# BRAINCHIP.net
KiCad netlist of a schematic drawn in EAGLE
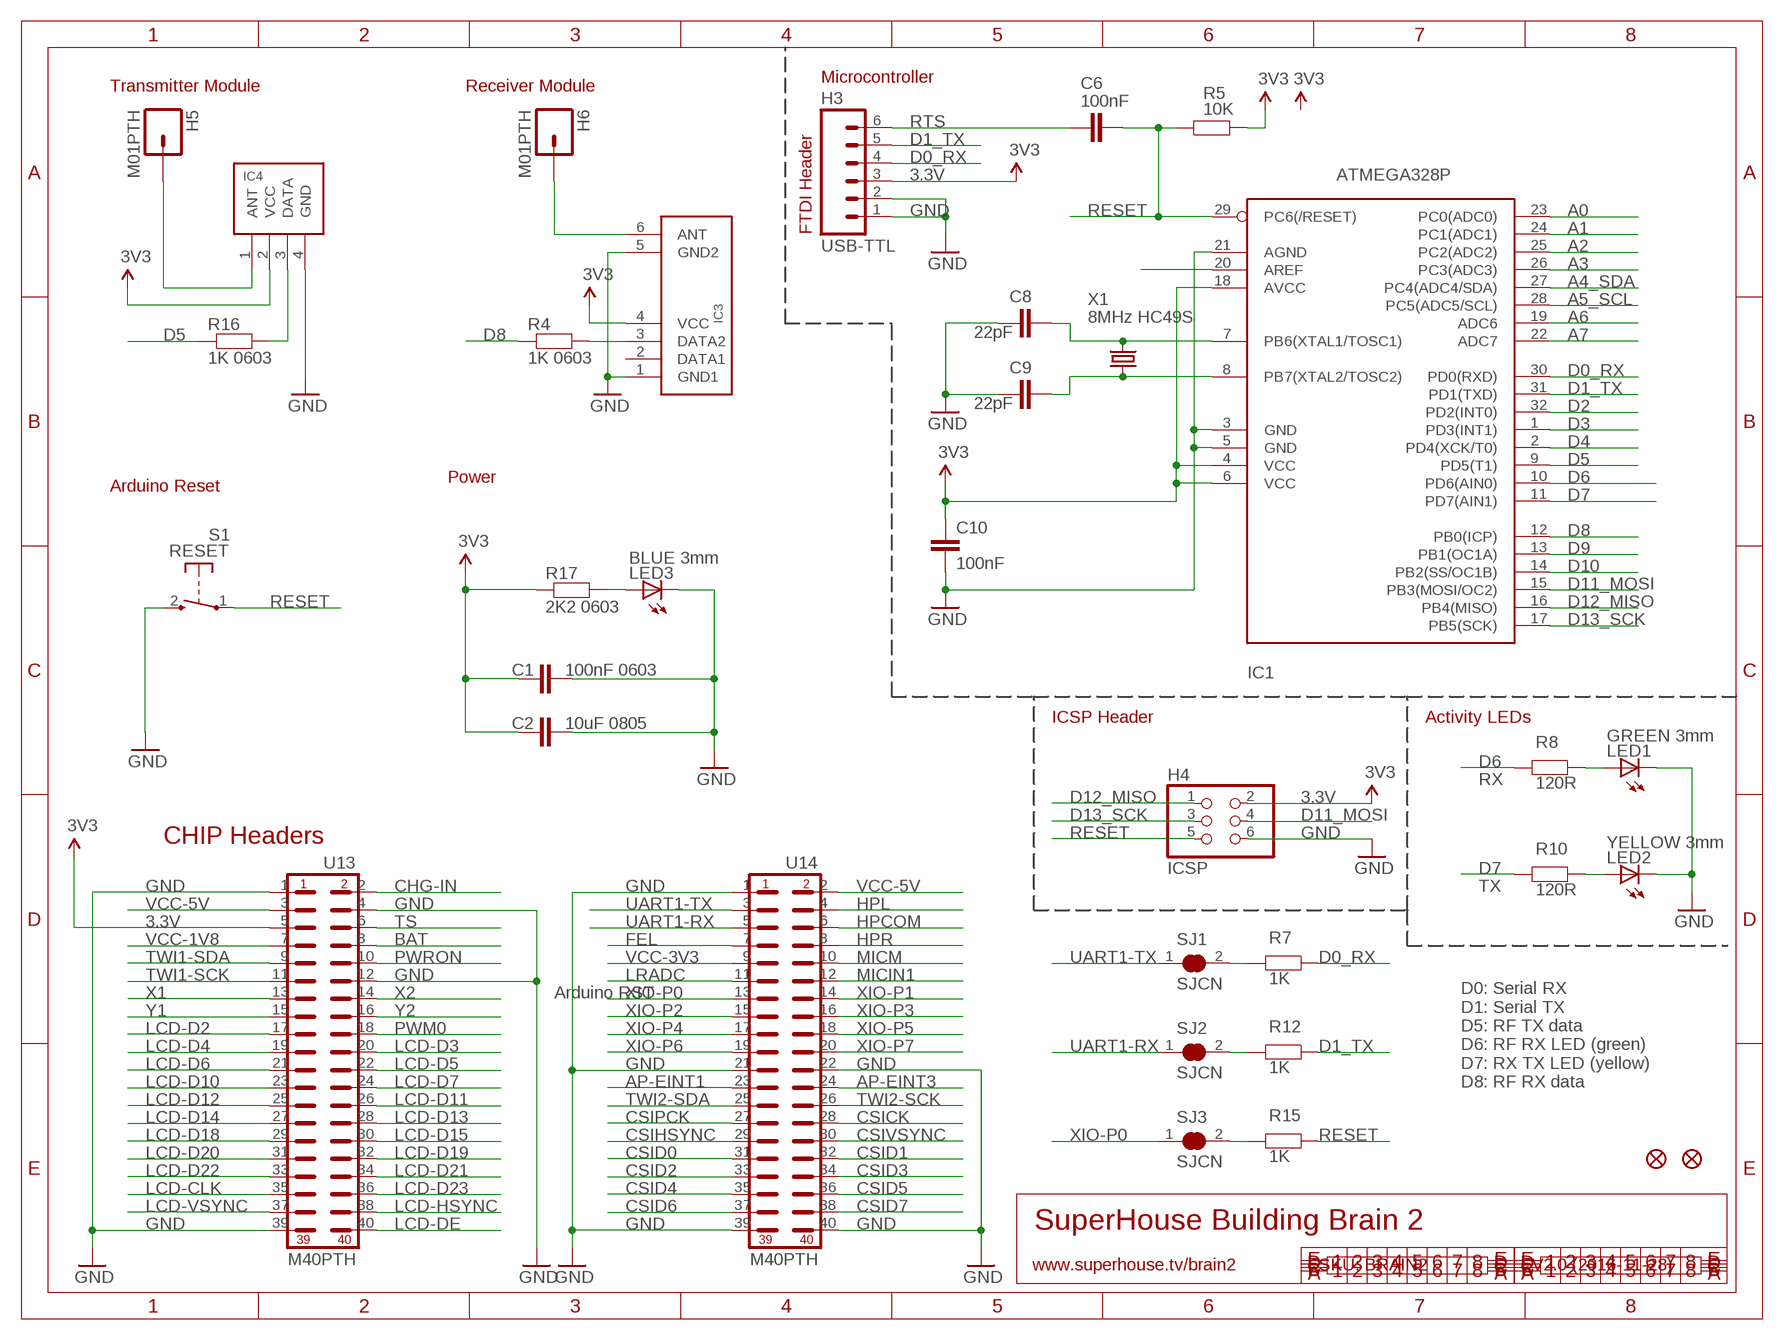
[diagram p0: schematic, sheet 1]

(export (version "E")
  (design (tool "Eeschema 10.0.6"))
  (components
    (comp (ref "C1")
      (value "100nF 0603")
      (footprint "eagle-import:0603")
      (libsource (lib "eagle-import") (part "CAP0603"))
    )
    (comp (ref "C2")
      (value "10uF 0805")
      (footprint "eagle-import:C0805")
      (libsource (lib "eagle-import") (part "C-EUC0805"))
    )
    (comp (ref "C6")
      (value "100nF")
      (footprint "eagle-import:0603")
      (libsource (lib "eagle-import") (part "freetronics-master-v1.1_CAP0603"))
    )
    (comp (ref "C8")
      (value "22pF")
      (footprint "eagle-import:0603")
      (libsource (lib "eagle-import") (part "freetronics-master-v1.1_CAP0603"))
    )
    (comp (ref "C9")
      (value "22pF")
      (footprint "eagle-import:0603")
      (libsource (lib "eagle-import") (part "freetronics-master-v1.1_CAP0603"))
    )
    (comp (ref "C10")
      (value "100nF")
      (footprint "eagle-import:0603")
      (libsource (lib "eagle-import") (part "freetronics-master-v1.1_CAP0603"))
    )
    (comp (ref "H3")
      (value "USB-TTL")
      (footprint "eagle-import:1X06")
      (libsource (lib "eagle-import") (part "M06SIP"))
    )
    (comp (ref "H4")
      (value "ICSP")
      (footprint "eagle-import:2X03")
      (libsource (lib "eagle-import") (part "PINHD-2X3"))
    )
    (comp (ref "H5")
      (value "M01PTH")
      (footprint "eagle-import:1X01")
      (libsource (lib "eagle-import") (part "M01PTH"))
    )
    (comp (ref "H6")
      (value "M01PTH")
      (footprint "eagle-import:1X01")
      (libsource (lib "eagle-import") (part "M01PTH"))
    )
    (comp (ref "IC1")
      (value "ATMEGA328P")
      (footprint "eagle-import:TQFP32-08")
      (libsource (lib "eagle-import") (part "AVR-MEGA8-AI"))
    )
    (comp (ref "IC3")
      (value "RXB1")
      (footprint "eagle-import:RX-B1-SHORT-FLAT")
      (libsource (lib "eagle-import") (part "RXB1SHORTFLAT"))
    )
    (comp (ref "IC4")
      (value "TX-C1FLAT")
      (footprint "eagle-import:TX-C1-FLAT")
      (libsource (lib "eagle-import") (part "TX-C1FLAT"))
    )
    (comp (ref "LED1")
      (value "GREEN 3mm")
      (footprint "eagle-import:LED3MM")
      (libsource (lib "eagle-import") (part "LED3MM"))
    )
    (comp (ref "LED2")
      (value "YELLOW 3mm")
      (footprint "eagle-import:LED3MM")
      (libsource (lib "eagle-import") (part "LED3MM"))
    )
    (comp (ref "LED3")
      (value "BLUE 3mm")
      (footprint "eagle-import:LED3MM")
      (libsource (lib "eagle-import") (part "LED3MM"))
    )
    (comp (ref "R4")
      (value "1K 0603")
      (footprint "eagle-import:0603")
      (libsource (lib "eagle-import") (part "RESISTOR0603"))
    )
    (comp (ref "R5")
      (value "10K")
      (footprint "eagle-import:0603")
      (libsource (lib "eagle-import") (part "freetronics-master-v1.1_RESISTOR0603"))
    )
    (comp (ref "R7")
      (value "1K")
      (footprint "eagle-import:0603")
      (libsource (lib "eagle-import") (part "freetronics-master-v1.1_RESISTOR0603"))
    )
    (comp (ref "R8")
      (value "120R")
      (footprint "eagle-import:0603")
      (libsource (lib "eagle-import") (part "freetronics-master-v1.1_RESISTOR0603"))
    )
    (comp (ref "R10")
      (value "120R")
      (footprint "eagle-import:0603")
      (libsource (lib "eagle-import") (part "freetronics-master-v1.1_RESISTOR0603"))
    )
    (comp (ref "R12")
      (value "1K")
      (footprint "eagle-import:0603")
      (libsource (lib "eagle-import") (part "freetronics-master-v1.1_RESISTOR0603"))
    )
    (comp (ref "R15")
      (value "1K")
      (footprint "eagle-import:0603")
      (libsource (lib "eagle-import") (part "freetronics-master-v1.1_RESISTOR0603"))
    )
    (comp (ref "R16")
      (value "1K 0603")
      (footprint "eagle-import:0603")
      (libsource (lib "eagle-import") (part "RESISTOR0603"))
    )
    (comp (ref "R17")
      (value "2K2 0603")
      (footprint "eagle-import:0603")
      (libsource (lib "eagle-import") (part "RESISTOR0603"))
    )
    (comp (ref "S1")
      (value "RESET")
      (footprint "eagle-import:TACTILE_SWITCH_SMD_2PIN_TINY")
      (libsource (lib "eagle-import") (part "TAC_SWITCH_2PIN"))
    )
    (comp (ref "SJ1")
      (value "SJCN")
      (footprint "eagle-import:SJC")
      (libsource (lib "eagle-import") (part "SJCN"))
    )
    (comp (ref "SJ2")
      (value "SJCN")
      (footprint "eagle-import:SJC")
      (libsource (lib "eagle-import") (part "SJCN"))
    )
    (comp (ref "SJ3")
      (value "SJCN")
      (footprint "eagle-import:SJC")
      (libsource (lib "eagle-import") (part "SJCN"))
    )
    (comp (ref "U$5")
      (value "FIDUCIAL1X2.5")
      (footprint "eagle-import:FIDUCIAL-1X2.5")
      (libsource (lib "eagle-import") (part "FIDUCIAL1X2.5"))
    )
    (comp (ref "U$6")
      (value "FIDUCIAL1X2.5")
      (footprint "eagle-import:FIDUCIAL-1X2.5")
      (libsource (lib "eagle-import") (part "FIDUCIAL1X2.5"))
    )
    (comp (ref "U13")
      (value "M40PTH")
      (footprint "eagle-import:2X20")
      (libsource (lib "eagle-import") (part "M40PTH"))
    )
    (comp (ref "U14")
      (value "M40PTH")
      (footprint "eagle-import:2X20")
      (libsource (lib "eagle-import") (part "M40PTH"))
    )
    (comp (ref "X1")
      (value "8MHz HC49S")
      (footprint "eagle-import:HC49U-V")
      (libsource (lib "eagle-import") (part "CRYSTALHC49UV"))
    )
  )
  (nets
    (net (code "1") (name "/A0") (class "Default")
      (node (ref "IC1") (pin "23") (pinfunction "PC0(ADC0)_23") (pintype "bidirectional"))
    )
    (net (code "2") (name "/A1") (class "Default")
      (node (ref "IC1") (pin "24") (pinfunction "PC1(ADC1)_24") (pintype "bidirectional"))
    )
    (net (code "3") (name "/A2") (class "Default")
      (node (ref "IC1") (pin "25") (pinfunction "PC2(ADC2)_25") (pintype "bidirectional"))
    )
    (net (code "4") (name "/A3") (class "Default")
      (node (ref "IC1") (pin "26") (pinfunction "PC3(ADC3)_26") (pintype "bidirectional"))
    )
    (net (code "5") (name "/A4_SDA") (class "Default")
      (node (ref "IC1") (pin "27") (pinfunction "PC4(ADC4/SDA)_27") (pintype "bidirectional"))
    )
    (net (code "6") (name "/A5_SCL") (class "Default")
      (node (ref "IC1") (pin "28") (pinfunction "PC5(ADC5/SCL)_28") (pintype "bidirectional"))
    )
    (net (code "7") (name "/A6") (class "Default")
      (node (ref "IC1") (pin "19") (pinfunction "ADC6_19") (pintype "bidirectional"))
    )
    (net (code "8") (name "/A7") (class "Default")
      (node (ref "IC1") (pin "22") (pinfunction "ADC7_22") (pintype "bidirectional"))
    )
    (net (code "9") (name "/AP-EINT1") (class "Default")
      (node (ref "U14") (pin "23") (pinfunction "23_23") (pintype "passive"))
    )
    (net (code "10") (name "/AP-EINT3") (class "Default")
      (node (ref "U14") (pin "24") (pinfunction "24_24") (pintype "passive"))
    )
    (net (code "11") (name "/BAT") (class "Default")
      (node (ref "U13") (pin "8") (pinfunction "8_8") (pintype "passive"))
    )
    (net (code "12") (name "/CHG-IN") (class "Default")
      (node (ref "U13") (pin "2") (pinfunction "2_2") (pintype "passive"))
    )
    (net (code "13") (name "/CSICK") (class "Default")
      (node (ref "U14") (pin "28") (pinfunction "28_28") (pintype "passive"))
    )
    (net (code "14") (name "/CSID0") (class "Default")
      (node (ref "U14") (pin "31") (pinfunction "31_31") (pintype "passive"))
    )
    (net (code "15") (name "/CSID1") (class "Default")
      (node (ref "U14") (pin "32") (pinfunction "32_32") (pintype "passive"))
    )
    (net (code "16") (name "/CSID2") (class "Default")
      (node (ref "U14") (pin "33") (pinfunction "33_33") (pintype "passive"))
    )
    (net (code "17") (name "/CSID3") (class "Default")
      (node (ref "U14") (pin "34") (pinfunction "34_34") (pintype "passive"))
    )
    (net (code "18") (name "/CSID4") (class "Default")
      (node (ref "U14") (pin "35") (pinfunction "35_35") (pintype "passive"))
    )
    (net (code "19") (name "/CSID5") (class "Default")
      (node (ref "U14") (pin "36") (pinfunction "36_36") (pintype "passive"))
    )
    (net (code "20") (name "/CSID6") (class "Default")
      (node (ref "U14") (pin "37") (pinfunction "37_37") (pintype "passive"))
    )
    (net (code "21") (name "/CSID7") (class "Default")
      (node (ref "U14") (pin "38") (pinfunction "38_38") (pintype "passive"))
    )
    (net (code "22") (name "/CSIHSYNC") (class "Default")
      (node (ref "U14") (pin "29") (pinfunction "29_29") (pintype "passive"))
    )
    (net (code "23") (name "/CSIPCK") (class "Default")
      (node (ref "U14") (pin "27") (pinfunction "27_27") (pintype "passive"))
    )
    (net (code "24") (name "/CSIVSYNC") (class "Default")
      (node (ref "U14") (pin "30") (pinfunction "30_30") (pintype "passive"))
    )
    (net (code "25") (name "/D0_RX") (class "Default")
      (node (ref "H3") (pin "4") (pinfunction "4_4") (pintype "passive"))
      (node (ref "IC1") (pin "30") (pinfunction "PD0(RXD)_30") (pintype "bidirectional"))
      (node (ref "R7") (pin "1") (pinfunction "1_1") (pintype "passive"))
    )
    (net (code "26") (name "/D1_TX") (class "Default")
      (node (ref "H3") (pin "5") (pinfunction "5_5") (pintype "passive"))
      (node (ref "IC1") (pin "31") (pinfunction "PD1(TXD)_31") (pintype "bidirectional"))
      (node (ref "R12") (pin "1") (pinfunction "1_1") (pintype "passive"))
    )
    (net (code "27") (name "/D2") (class "Default")
      (node (ref "IC1") (pin "32") (pinfunction "PD2(INT0)_32") (pintype "bidirectional"))
    )
    (net (code "28") (name "/D3") (class "Default")
      (node (ref "IC1") (pin "1") (pinfunction "PD3(INT1)_1") (pintype "bidirectional"))
    )
    (net (code "29") (name "/D4") (class "Default")
      (node (ref "IC1") (pin "2") (pinfunction "PD4(XCK/T0)_2") (pintype "bidirectional"))
    )
    (net (code "30") (name "/D5") (class "Default")
      (node (ref "IC1") (pin "9") (pinfunction "PD5(T1)_9") (pintype "bidirectional"))
      (node (ref "R16") (pin "1") (pinfunction "1_1") (pintype "passive"))
    )
    (net (code "31") (name "/D6") (class "Default")
      (node (ref "IC1") (pin "10") (pinfunction "PD6(AIN0)_10") (pintype "bidirectional"))
      (node (ref "R8") (pin "2") (pinfunction "2_2") (pintype "passive"))
    )
    (net (code "32") (name "/D7") (class "Default")
      (node (ref "IC1") (pin "11") (pinfunction "PD7(AIN1)_11") (pintype "bidirectional"))
      (node (ref "R10") (pin "2") (pinfunction "2_2") (pintype "passive"))
    )
    (net (code "33") (name "/D8") (class "Default")
      (node (ref "IC1") (pin "12") (pinfunction "PB0(ICP)_12") (pintype "bidirectional"))
      (node (ref "R4") (pin "1") (pinfunction "1_1") (pintype "passive"))
    )
    (net (code "34") (name "/D9") (class "Default")
      (node (ref "IC1") (pin "13") (pinfunction "PB1(OC1A)_13") (pintype "bidirectional"))
    )
    (net (code "35") (name "/D10") (class "Default")
      (node (ref "IC1") (pin "14") (pinfunction "PB2(SS/OC1B)_14") (pintype "bidirectional"))
    )
    (net (code "36") (name "/D11_MOSI") (class "Default")
      (node (ref "H4") (pin "4") (pinfunction "4_4") (pintype "passive"))
      (node (ref "IC1") (pin "15") (pinfunction "PB3(MOSI/OC2)_15") (pintype "bidirectional"))
    )
    (net (code "37") (name "/D12_MISO") (class "Default")
      (node (ref "H4") (pin "1") (pinfunction "1_1") (pintype "passive"))
      (node (ref "IC1") (pin "16") (pinfunction "PB4(MISO)_16") (pintype "bidirectional"))
    )
    (net (code "38") (name "/D13_SCK") (class "Default")
      (node (ref "H4") (pin "3") (pinfunction "3_3") (pintype "passive"))
      (node (ref "IC1") (pin "17") (pinfunction "PB5(SCK)_17") (pintype "bidirectional"))
    )
    (net (code "39") (name "/FEL") (class "Default")
      (node (ref "U14") (pin "7") (pinfunction "7_7") (pintype "passive"))
    )
    (net (code "40") (name "/HPCOM") (class "Default")
      (node (ref "U14") (pin "6") (pinfunction "6_6") (pintype "passive"))
    )
    (net (code "41") (name "/HPL") (class "Default")
      (node (ref "U14") (pin "4") (pinfunction "4_4") (pintype "passive"))
    )
    (net (code "42") (name "/HPR") (class "Default")
      (node (ref "U14") (pin "8") (pinfunction "8_8") (pintype "passive"))
    )
    (net (code "43") (name "/LCD-CLK") (class "Default")
      (node (ref "U13") (pin "35") (pinfunction "35_35") (pintype "passive"))
    )
    (net (code "44") (name "/LCD-D2") (class "Default")
      (node (ref "U13") (pin "17") (pinfunction "17_17") (pintype "passive"))
    )
    (net (code "45") (name "/LCD-D3") (class "Default")
      (node (ref "U13") (pin "20") (pinfunction "20_20") (pintype "passive"))
    )
    (net (code "46") (name "/LCD-D4") (class "Default")
      (node (ref "U13") (pin "19") (pinfunction "19_19") (pintype "passive"))
    )
    (net (code "47") (name "/LCD-D5") (class "Default")
      (node (ref "U13") (pin "22") (pinfunction "22_22") (pintype "passive"))
    )
    (net (code "48") (name "/LCD-D6") (class "Default")
      (node (ref "U13") (pin "21") (pinfunction "21_21") (pintype "passive"))
    )
    (net (code "49") (name "/LCD-D7") (class "Default")
      (node (ref "U13") (pin "24") (pinfunction "24_24") (pintype "passive"))
    )
    (net (code "50") (name "/LCD-D10") (class "Default")
      (node (ref "U13") (pin "23") (pinfunction "23_23") (pintype "passive"))
    )
    (net (code "51") (name "/LCD-D11") (class "Default")
      (node (ref "U13") (pin "26") (pinfunction "26_26") (pintype "passive"))
    )
    (net (code "52") (name "/LCD-D12") (class "Default")
      (node (ref "U13") (pin "25") (pinfunction "25_25") (pintype "passive"))
    )
    (net (code "53") (name "/LCD-D13") (class "Default")
      (node (ref "U13") (pin "28") (pinfunction "28_28") (pintype "passive"))
    )
    (net (code "54") (name "/LCD-D14") (class "Default")
      (node (ref "U13") (pin "27") (pinfunction "27_27") (pintype "passive"))
    )
    (net (code "55") (name "/LCD-D15") (class "Default")
      (node (ref "U13") (pin "30") (pinfunction "30_30") (pintype "passive"))
    )
    (net (code "56") (name "/LCD-D18") (class "Default")
      (node (ref "U13") (pin "29") (pinfunction "29_29") (pintype "passive"))
    )
    (net (code "57") (name "/LCD-D19") (class "Default")
      (node (ref "U13") (pin "32") (pinfunction "32_32") (pintype "passive"))
    )
    (net (code "58") (name "/LCD-D20") (class "Default")
      (node (ref "U13") (pin "31") (pinfunction "31_31") (pintype "passive"))
    )
    (net (code "59") (name "/LCD-D21") (class "Default")
      (node (ref "U13") (pin "34") (pinfunction "34_34") (pintype "passive"))
    )
    (net (code "60") (name "/LCD-D22") (class "Default")
      (node (ref "U13") (pin "33") (pinfunction "33_33") (pintype "passive"))
    )
    (net (code "61") (name "/LCD-D23") (class "Default")
      (node (ref "U13") (pin "36") (pinfunction "36_36") (pintype "passive"))
    )
    (net (code "62") (name "/LCD-DE") (class "Default")
      (node (ref "U13") (pin "40") (pinfunction "40_40") (pintype "passive"))
    )
    (net (code "63") (name "/LCD-HSYNC") (class "Default")
      (node (ref "U13") (pin "38") (pinfunction "38_38") (pintype "passive"))
    )
    (net (code "64") (name "/LCD-VSYNC") (class "Default")
      (node (ref "U13") (pin "37") (pinfunction "37_37") (pintype "passive"))
    )
    (net (code "65") (name "/LRADC") (class "Default")
      (node (ref "U14") (pin "11") (pinfunction "11_11") (pintype "passive"))
    )
    (net (code "66") (name "/MICIN1") (class "Default")
      (node (ref "U14") (pin "12") (pinfunction "12_12") (pintype "passive"))
    )
    (net (code "67") (name "/MICM") (class "Default")
      (node (ref "U14") (pin "10") (pinfunction "10_10") (pintype "passive"))
    )
    (net (code "68") (name "/PWM0") (class "Default")
      (node (ref "U13") (pin "18") (pinfunction "18_18") (pintype "passive"))
    )
    (net (code "69") (name "/PWRON") (class "Default")
      (node (ref "U13") (pin "10") (pinfunction "10_10") (pintype "passive"))
    )
    (net (code "70") (name "/RESET") (class "Default")
      (node (ref "C6") (pin "2") (pinfunction "2_2") (pintype "passive"))
      (node (ref "H4") (pin "5") (pinfunction "5_5") (pintype "passive"))
      (node (ref "IC1") (pin "29") (pinfunction "PC6(/RESET)_29") (pintype "bidirectional"))
      (node (ref "R15") (pin "1") (pinfunction "1_1") (pintype "passive"))
      (node (ref "R5") (pin "1") (pinfunction "1_1") (pintype "passive"))
      (node (ref "S1") (pin "1") (pinfunction "P_1") (pintype "passive"))
    )
    (net (code "71") (name "/RTS") (class "Default")
      (node (ref "C6") (pin "1") (pinfunction "1_1") (pintype "passive"))
      (node (ref "H3") (pin "6") (pinfunction "6_6") (pintype "passive"))
    )
    (net (code "72") (name "/TS") (class "Default")
      (node (ref "U13") (pin "6") (pinfunction "6_6") (pintype "passive"))
    )
    (net (code "73") (name "/TWI1-SCK") (class "Default")
      (node (ref "U13") (pin "11") (pinfunction "11_11") (pintype "passive"))
    )
    (net (code "74") (name "/TWI1-SDA") (class "Default")
      (node (ref "U13") (pin "9") (pinfunction "9_9") (pintype "passive"))
    )
    (net (code "75") (name "/TWI2-SCK") (class "Default")
      (node (ref "U14") (pin "26") (pinfunction "26_26") (pintype "passive"))
    )
    (net (code "76") (name "/TWI2-SDA") (class "Default")
      (node (ref "U14") (pin "25") (pinfunction "25_25") (pintype "passive"))
    )
    (net (code "77") (name "/UART1-RX") (class "Default")
      (node (ref "SJ2") (pin "1") (pinfunction "1_1") (pintype "passive"))
      (node (ref "U14") (pin "5") (pinfunction "5_5") (pintype "passive"))
    )
    (net (code "78") (name "/UART1-TX") (class "Default")
      (node (ref "SJ1") (pin "1") (pinfunction "1_1") (pintype "passive"))
      (node (ref "U14") (pin "3") (pinfunction "3_3") (pintype "passive"))
    )
    (net (code "79") (name "/VCC-1V8") (class "Default")
      (node (ref "U13") (pin "7") (pinfunction "7_7") (pintype "passive"))
    )
    (net (code "80") (name "/VCC-3V3") (class "Default")
      (node (ref "U14") (pin "9") (pinfunction "9_9") (pintype "passive"))
    )
    (net (code "81") (name "/VCC-5V") (class "Default")
      (node (ref "U13") (pin "3") (pinfunction "3_3") (pintype "passive"))
      (node (ref "U14") (pin "2") (pinfunction "2_2") (pintype "passive"))
    )
    (net (code "82") (name "/X1") (class "Default")
      (node (ref "U13") (pin "13") (pinfunction "13_13") (pintype "passive"))
    )
    (net (code "83") (name "/X2") (class "Default")
      (node (ref "U13") (pin "14") (pinfunction "14_14") (pintype "passive"))
    )
    (net (code "84") (name "/XIO-P0") (class "Default")
      (node (ref "SJ3") (pin "1") (pinfunction "1_1") (pintype "passive"))
      (node (ref "U14") (pin "13") (pinfunction "13_13") (pintype "passive"))
    )
    (net (code "85") (name "/XIO-P1") (class "Default")
      (node (ref "U14") (pin "14") (pinfunction "14_14") (pintype "passive"))
    )
    (net (code "86") (name "/XIO-P2") (class "Default")
      (node (ref "U14") (pin "15") (pinfunction "15_15") (pintype "passive"))
    )
    (net (code "87") (name "/XIO-P3") (class "Default")
      (node (ref "U14") (pin "16") (pinfunction "16_16") (pintype "passive"))
    )
    (net (code "88") (name "/XIO-P4") (class "Default")
      (node (ref "U14") (pin "17") (pinfunction "17_17") (pintype "passive"))
    )
    (net (code "89") (name "/XIO-P5") (class "Default")
      (node (ref "U14") (pin "18") (pinfunction "18_18") (pintype "passive"))
    )
    (net (code "90") (name "/XIO-P6") (class "Default")
      (node (ref "U14") (pin "19") (pinfunction "19_19") (pintype "passive"))
    )
    (net (code "91") (name "/XIO-P7") (class "Default")
      (node (ref "U14") (pin "20") (pinfunction "20_20") (pintype "passive"))
    )
    (net (code "92") (name "/Y1") (class "Default")
      (node (ref "U13") (pin "15") (pinfunction "15_15") (pintype "passive"))
    )
    (net (code "93") (name "/Y2") (class "Default")
      (node (ref "U13") (pin "16") (pinfunction "16_16") (pintype "passive"))
    )
    (net (code "94") (name "3V3") (class "Default")
      (node (ref "C1") (pin "1") (pinfunction "1_1") (pintype "passive"))
      (node (ref "C10") (pin "1") (pinfunction "1_1") (pintype "passive"))
      (node (ref "C2") (pin "2") (pinfunction "2_2") (pintype "passive"))
      (node (ref "H3") (pin "3") (pinfunction "3_3") (pintype "passive"))
      (node (ref "H4") (pin "2") (pinfunction "2_2") (pintype "passive"))
      (node (ref "IC1") (pin "18") (pinfunction "AVCC_18") (pintype "bidirectional"))
      (node (ref "IC1") (pin "4") (pinfunction "VCC_4") (pintype "bidirectional"))
      (node (ref "IC1") (pin "6") (pinfunction "VCC_6") (pintype "bidirectional"))
      (node (ref "IC3") (pin "4") (pinfunction "VCC_4") (pintype "bidirectional"))
      (node (ref "IC4") (pin "2") (pinfunction "VCC_2") (pintype "power_in"))
      (node (ref "R17") (pin "1") (pinfunction "1_1") (pintype "passive"))
      (node (ref "R5") (pin "2") (pinfunction "2_2") (pintype "passive"))
      (node (ref "U13") (pin "5") (pinfunction "5_5") (pintype "passive"))
    )
    (net (code "95") (name "GND") (class "Default")
      (node (ref "C1") (pin "2") (pinfunction "2_2") (pintype "passive"))
      (node (ref "C10") (pin "2") (pinfunction "2_2") (pintype "passive"))
      (node (ref "C2") (pin "1") (pinfunction "1_1") (pintype "passive"))
      (node (ref "C8") (pin "1") (pinfunction "1_1") (pintype "passive"))
      (node (ref "C9") (pin "1") (pinfunction "1_1") (pintype "passive"))
      (node (ref "H3") (pin "1") (pinfunction "1_1") (pintype "passive"))
      (node (ref "H3") (pin "2") (pinfunction "2_2") (pintype "passive"))
      (node (ref "H4") (pin "6") (pinfunction "6_6") (pintype "passive"))
      (node (ref "IC1") (pin "21") (pinfunction "AGND_21") (pintype "bidirectional"))
      (node (ref "IC1") (pin "3") (pinfunction "GND_3") (pintype "bidirectional"))
      (node (ref "IC1") (pin "5") (pinfunction "GND_5") (pintype "bidirectional"))
      (node (ref "IC3") (pin "1") (pinfunction "GND1_1") (pintype "bidirectional"))
      (node (ref "IC3") (pin "5") (pinfunction "GND2_5") (pintype "bidirectional"))
      (node (ref "IC4") (pin "4") (pinfunction "GND_4") (pintype "power_in"))
      (node (ref "LED1") (pin "K") (pinfunction "C_K") (pintype "passive"))
      (node (ref "LED2") (pin "K") (pinfunction "C_K") (pintype "passive"))
      (node (ref "LED3") (pin "K") (pinfunction "C_K") (pintype "passive"))
      (node (ref "S1") (pin "2") (pinfunction "S_2") (pintype "passive"))
      (node (ref "U13") (pin "1") (pinfunction "1_1") (pintype "passive"))
      (node (ref "U13") (pin "12") (pinfunction "12_12") (pintype "passive"))
      (node (ref "U13") (pin "39") (pinfunction "39_39") (pintype "passive"))
      (node (ref "U13") (pin "4") (pinfunction "4_4") (pintype "passive"))
      (node (ref "U14") (pin "1") (pinfunction "1_1") (pintype "passive"))
      (node (ref "U14") (pin "21") (pinfunction "21_21") (pintype "passive"))
      (node (ref "U14") (pin "22") (pinfunction "22_22") (pintype "passive"))
      (node (ref "U14") (pin "39") (pinfunction "39_39") (pintype "passive"))
      (node (ref "U14") (pin "40") (pinfunction "40_40") (pintype "passive"))
    )
    (net (code "96") (name "Net-(IC1-PB6(XTAL1{slash}TOSC1))") (class "Default")
      (node (ref "C8") (pin "2") (pinfunction "2_2") (pintype "passive"))
      (node (ref "IC1") (pin "7") (pinfunction "PB6(XTAL1/TOSC1)_7") (pintype "bidirectional"))
      (node (ref "X1") (pin "2") (pinfunction "2_2") (pintype "passive"))
    )
    (net (code "97") (name "Net-(IC1-PB7(XTAL2{slash}TOSC2))") (class "Default")
      (node (ref "C9") (pin "2") (pinfunction "2_2") (pintype "passive"))
      (node (ref "IC1") (pin "8") (pinfunction "PB7(XTAL2/TOSC2)_8") (pintype "bidirectional"))
      (node (ref "X1") (pin "1") (pinfunction "1_1") (pintype "passive"))
    )
    (net (code "98") (name "Net-(IC3-ANT)") (class "Default")
      (node (ref "H6") (pin "1") (pinfunction "1_1") (pintype "passive"))
      (node (ref "IC3") (pin "6") (pinfunction "ANT_6") (pintype "bidirectional"))
    )
    (net (code "99") (name "Net-(IC3-DATA2)") (class "Default")
      (node (ref "IC3") (pin "3") (pinfunction "DATA2_3") (pintype "bidirectional"))
      (node (ref "R4") (pin "2") (pinfunction "2_2") (pintype "passive"))
    )
    (net (code "100") (name "Net-(IC4-ANT)") (class "Default")
      (node (ref "H5") (pin "1") (pinfunction "1_1") (pintype "passive"))
      (node (ref "IC4") (pin "1") (pinfunction "ANT_1") (pintype "output"))
    )
    (net (code "101") (name "Net-(IC4-DATA)") (class "Default")
      (node (ref "IC4") (pin "3") (pinfunction "DATA_3") (pintype "input"))
      (node (ref "R16") (pin "2") (pinfunction "2_2") (pintype "passive"))
    )
    (net (code "102") (name "Net-(LED1-PadA)") (class "Default")
      (node (ref "LED1") (pin "A") (pinfunction "A_A") (pintype "passive"))
      (node (ref "R8") (pin "1") (pinfunction "1_1") (pintype "passive"))
    )
    (net (code "103") (name "Net-(LED2-PadA)") (class "Default")
      (node (ref "LED2") (pin "A") (pinfunction "A_A") (pintype "passive"))
      (node (ref "R10") (pin "1") (pinfunction "1_1") (pintype "passive"))
    )
    (net (code "104") (name "Net-(LED3-PadA)") (class "Default")
      (node (ref "LED3") (pin "A") (pinfunction "A_A") (pintype "passive"))
      (node (ref "R17") (pin "2") (pinfunction "2_2") (pintype "passive"))
    )
    (net (code "105") (name "Net-(R7-Pad2)") (class "Default")
      (node (ref "R7") (pin "2") (pinfunction "2_2") (pintype "passive"))
      (node (ref "SJ1") (pin "2") (pinfunction "2_2") (pintype "passive"))
    )
    (net (code "106") (name "Net-(R12-Pad2)") (class "Default")
      (node (ref "R12") (pin "2") (pinfunction "2_2") (pintype "passive"))
      (node (ref "SJ2") (pin "2") (pinfunction "2_2") (pintype "passive"))
    )
    (net (code "107") (name "Net-(R15-Pad2)") (class "Default")
      (node (ref "R15") (pin "2") (pinfunction "2_2") (pintype "passive"))
      (node (ref "SJ3") (pin "2") (pinfunction "2_2") (pintype "passive"))
    )
    (net (code "108") (name "unconnected-(IC1-AREF-Pad20)") (class "Default")
      (node (ref "IC1") (pin "20") (pinfunction "AREF_20") (pintype "bidirectional"))
    )
    (net (code "109") (name "unconnected-(IC3-DATA1-Pad2)") (class "Default")
      (node (ref "IC3") (pin "2") (pinfunction "DATA1_2") (pintype "bidirectional"))
    )
  )
)
